# pcb.net
KiCad netlist of a schematic drawn in EAGLE
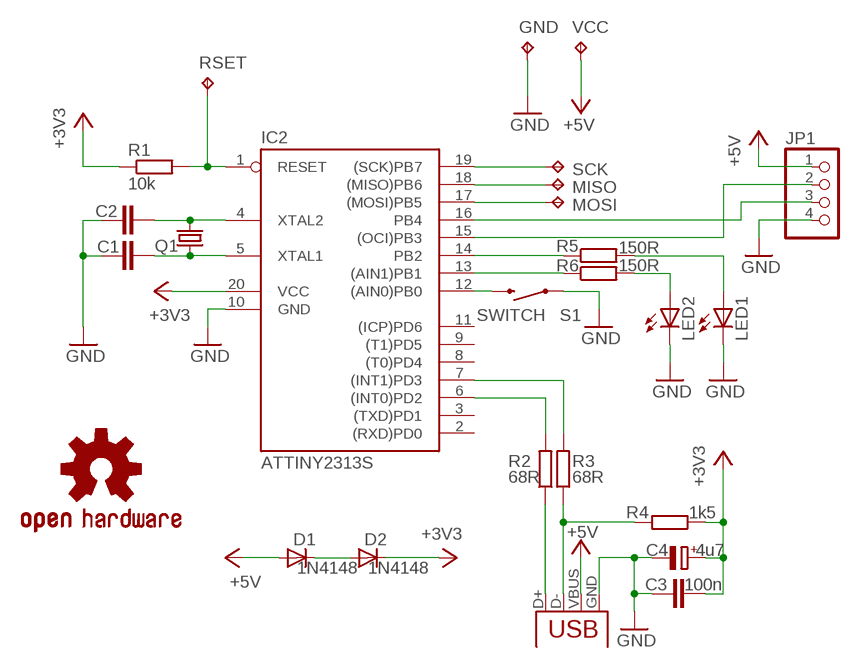
[diagram p0: schematic, sheet 1]

(export (version "E")
  (design (tool "Eeschema 10.0.6"))
  (components
    (comp (ref "C1")
      (value "C-EUC1206")
      (footprint "eagle-import:C1206")
      (libsource (lib "eagle-import") (part "C-EUC1206"))
    )
    (comp (ref "C2")
      (value "C-EUC1206")
      (footprint "eagle-import:C1206")
      (libsource (lib "eagle-import") (part "C-EUC1206"))
    )
    (comp (ref "C3")
      (value "100n")
      (footprint "eagle-import:C1206")
      (libsource (lib "eagle-import") (part "C-EUC1206"))
    )
    (comp (ref "C4")
      (value "4u7")
      (footprint "eagle-import:PANASONIC_B")
      (libsource (lib "eagle-import") (part "CPOL-EUB"))
    )
    (comp (ref "D1")
      (value "1N4148")
      (footprint "eagle-import:SMA-DIODE")
      (libsource (lib "eagle-import") (part "DIODESMA"))
    )
    (comp (ref "D2")
      (value "1N4148")
      (footprint "eagle-import:SMA-DIODE")
      (libsource (lib "eagle-import") (part "DIODESMA"))
    )
    (comp (ref "GND")
      (value "TPB2,54")
      (footprint "eagle-import:B2,54")
      (libsource (lib "eagle-import") (part "TPB2,54"))
    )
    (comp (ref "IC2")
      (value "ATTINY2313S")
      (footprint "eagle-import:SO20L")
      (libsource (lib "eagle-import") (part "AT90S2313S"))
    )
    (comp (ref "JP1")
      (value "PINHD-1X4_2.54")
      (footprint "eagle-import:1X04")
      (libsource (lib "eagle-import") (part "PINHD-1X4_2.54"))
    )
    (comp (ref "LED1")
      (value "LED1206")
      (footprint "eagle-import:LED-1206")
      (libsource (lib "eagle-import") (part "LED1206"))
    )
    (comp (ref "LED2")
      (value "LED1206")
      (footprint "eagle-import:LED-1206")
      (libsource (lib "eagle-import") (part "LED1206"))
    )
    (comp (ref "LOGO1")
      (value "OSHW-LOGOM")
      (footprint "eagle-import:OSHW-LOGO-M")
      (libsource (lib "eagle-import") (part "OSHW-LOGOM"))
    )
    (comp (ref "MISO")
      (value "TPB2,54")
      (footprint "eagle-import:B2,54")
      (libsource (lib "eagle-import") (part "TPB2,54"))
    )
    (comp (ref "MOSI")
      (value "TPB2,54")
      (footprint "eagle-import:B2,54")
      (libsource (lib "eagle-import") (part "TPB2,54"))
    )
    (comp (ref "Q1")
      (value "CRYSTALSMD")
      (footprint "eagle-import:HC49UP")
      (libsource (lib "eagle-import") (part "CRYSTALSMD"))
    )
    (comp (ref "R1")
      (value "10k")
      (footprint "eagle-import:R1206")
      (libsource (lib "eagle-import") (part "R-EU_R1206"))
    )
    (comp (ref "R2")
      (value "68R")
      (footprint "eagle-import:R1206")
      (libsource (lib "eagle-import") (part "R-EU_R1206"))
    )
    (comp (ref "R3")
      (value "68R")
      (footprint "eagle-import:R1206")
      (libsource (lib "eagle-import") (part "R-EU_R1206"))
    )
    (comp (ref "R4")
      (value "1k5")
      (footprint "eagle-import:R1206")
      (libsource (lib "eagle-import") (part "R-EU_R1206"))
    )
    (comp (ref "R5")
      (value "150R")
      (footprint "eagle-import:R1206")
      (libsource (lib "eagle-import") (part "R-EU_R1206"))
    )
    (comp (ref "R6")
      (value "150R")
      (footprint "eagle-import:R1206")
      (libsource (lib "eagle-import") (part "R-EU_R1206"))
    )
    (comp (ref "RSET")
      (value "TPB2,54")
      (footprint "eagle-import:B2,54")
      (libsource (lib "eagle-import") (part "TPB2,54"))
    )
    (comp (ref "S1")
      (value "SWITCH")
      (footprint "eagle-import:TACTILE-SWITCH-1101NE")
      (libsource (lib "eagle-import") (part "SWITCH-MOMENTARY-2-SMD-1101NE"))
    )
    (comp (ref "SCK")
      (value "TPB2,54")
      (footprint "eagle-import:B2,54")
      (libsource (lib "eagle-import") (part "TPB2,54"))
    )
    (comp (ref "VCC")
      (value "TPB2,54")
      (footprint "eagle-import:B2,54")
      (libsource (lib "eagle-import") (part "TPB2,54"))
    )
    (comp (ref "X1")
      (value "USB-MICROB")
      (footprint "eagle-import:USB-MICROB")
      (libsource (lib "eagle-import") (part "USB-MICROB"))
    )
  )
  (nets
    (net (code "1") (name "+3V3") (class "Default")
      (node (ref "C3") (pin "2") (pinfunction "2_2") (pintype "passive"))
      (node (ref "C4") (pin "+") (pinfunction "+_+") (pintype "passive"))
      (node (ref "D2") (pin "C") (pinfunction "C_C") (pintype "passive"))
      (node (ref "IC2") (pin "20") (pinfunction "VCC_20") (pintype "power_in"))
      (node (ref "R1") (pin "1") (pinfunction "1_1") (pintype "passive"))
      (node (ref "R4") (pin "1") (pinfunction "1_1") (pintype "passive"))
    )
    (net (code "2") (name "+5V") (class "Default")
      (node (ref "D1") (pin "A") (pinfunction "A_A") (pintype "passive"))
      (node (ref "JP1") (pin "1") (pinfunction "1_1") (pintype "passive"))
      (node (ref "VCC") (pin "TP") (pinfunction "TP_TP") (pintype "input"))
      (node (ref "X1") (pin "VBUS") (pinfunction "VBUS_VBUS") (pintype "bidirectional"))
    )
    (net (code "3") (name "GND") (class "Default")
      (node (ref "C1") (pin "1") (pinfunction "1_1") (pintype "passive"))
      (node (ref "C2") (pin "1") (pinfunction "1_1") (pintype "passive"))
      (node (ref "C3") (pin "1") (pinfunction "1_1") (pintype "passive"))
      (node (ref "C4") (pin "-") (pinfunction "-_-") (pintype "passive"))
      (node (ref "GND") (pin "TP") (pinfunction "TP_TP") (pintype "input"))
      (node (ref "IC2") (pin "10") (pinfunction "GND_10") (pintype "power_in"))
      (node (ref "JP1") (pin "4") (pinfunction "4_4") (pintype "passive"))
      (node (ref "LED1") (pin "C") (pinfunction "C_C") (pintype "passive"))
      (node (ref "LED2") (pin "C") (pinfunction "C_C") (pintype "passive"))
      (node (ref "S1") (pin "P$1") (pinfunction "1_P$1") (pintype "passive"))
      (node (ref "X1") (pin "GND") (pinfunction "GND_GND") (pintype "bidirectional"))
    )
    (net (code "4") (name "Net-(D1-PadC)") (class "Default")
      (node (ref "D1") (pin "C") (pinfunction "C_C") (pintype "passive"))
      (node (ref "D2") (pin "A") (pinfunction "A_A") (pintype "passive"))
    )
    (net (code "5") (name "Net-(IC2-(AIN0)PB0)") (class "Default")
      (node (ref "IC2") (pin "12") (pinfunction "(AIN0)PB0_12") (pintype "bidirectional"))
      (node (ref "S1") (pin "P$2") (pinfunction "2_P$2") (pintype "passive"))
    )
    (net (code "6") (name "Net-(IC2-(AIN1)PB1)") (class "Default")
      (node (ref "IC2") (pin "13") (pinfunction "(AIN1)PB1_13") (pintype "bidirectional"))
      (node (ref "R6") (pin "1") (pinfunction "1_1") (pintype "passive"))
    )
    (net (code "7") (name "Net-(IC2-(INT0)PD2)") (class "Default")
      (node (ref "IC2") (pin "6") (pinfunction "(INT0)PD2_6") (pintype "bidirectional"))
      (node (ref "R2") (pin "2") (pinfunction "2_2") (pintype "passive"))
    )
    (net (code "8") (name "Net-(IC2-(INT1)PD3)") (class "Default")
      (node (ref "IC2") (pin "7") (pinfunction "(INT1)PD3_7") (pintype "bidirectional"))
      (node (ref "R3") (pin "2") (pinfunction "2_2") (pintype "passive"))
    )
    (net (code "9") (name "Net-(IC2-(MISO)PB6)") (class "Default")
      (node (ref "IC2") (pin "18") (pinfunction "(MISO)PB6_18") (pintype "bidirectional"))
      (node (ref "MISO") (pin "TP") (pinfunction "TP_TP") (pintype "input"))
    )
    (net (code "10") (name "Net-(IC2-(MOSI)PB5)") (class "Default")
      (node (ref "IC2") (pin "17") (pinfunction "(MOSI)PB5_17") (pintype "bidirectional"))
      (node (ref "MOSI") (pin "TP") (pinfunction "TP_TP") (pintype "input"))
    )
    (net (code "11") (name "Net-(IC2-(OCI)PB3)") (class "Default")
      (node (ref "IC2") (pin "15") (pinfunction "(OCI)PB3_15") (pintype "bidirectional"))
      (node (ref "JP1") (pin "2") (pinfunction "2_2") (pintype "passive"))
    )
    (net (code "12") (name "Net-(IC2-(SCK)PB7)") (class "Default")
      (node (ref "IC2") (pin "19") (pinfunction "(SCK)PB7_19") (pintype "bidirectional"))
      (node (ref "SCK") (pin "TP") (pinfunction "TP_TP") (pintype "input"))
    )
    (net (code "13") (name "Net-(IC2-PB2)") (class "Default")
      (node (ref "IC2") (pin "14") (pinfunction "PB2_14") (pintype "bidirectional"))
      (node (ref "R5") (pin "1") (pinfunction "1_1") (pintype "passive"))
    )
    (net (code "14") (name "Net-(IC2-PB4)") (class "Default")
      (node (ref "IC2") (pin "16") (pinfunction "PB4_16") (pintype "bidirectional"))
      (node (ref "JP1") (pin "3") (pinfunction "3_3") (pintype "passive"))
    )
    (net (code "15") (name "Net-(IC2-RESET)") (class "Default")
      (node (ref "IC2") (pin "1") (pinfunction "RESET_1") (pintype "bidirectional"))
      (node (ref "R1") (pin "2") (pinfunction "2_2") (pintype "passive"))
      (node (ref "RSET") (pin "TP") (pinfunction "TP_TP") (pintype "input"))
    )
    (net (code "16") (name "Net-(IC2-XTAL1)") (class "Default")
      (node (ref "C1") (pin "2") (pinfunction "2_2") (pintype "passive"))
      (node (ref "IC2") (pin "5") (pinfunction "XTAL1_5") (pintype "bidirectional"))
      (node (ref "Q1") (pin "1") (pinfunction "1_1") (pintype "passive"))
    )
    (net (code "17") (name "Net-(IC2-XTAL2)") (class "Default")
      (node (ref "C2") (pin "2") (pinfunction "2_2") (pintype "passive"))
      (node (ref "IC2") (pin "4") (pinfunction "XTAL2_4") (pintype "bidirectional"))
      (node (ref "Q1") (pin "2") (pinfunction "2_2") (pintype "passive"))
    )
    (net (code "18") (name "Net-(LED1-PadA)") (class "Default")
      (node (ref "LED1") (pin "A") (pinfunction "A_A") (pintype "passive"))
      (node (ref "R5") (pin "2") (pinfunction "2_2") (pintype "passive"))
    )
    (net (code "19") (name "Net-(LED2-PadA)") (class "Default")
      (node (ref "LED2") (pin "A") (pinfunction "A_A") (pintype "passive"))
      (node (ref "R6") (pin "2") (pinfunction "2_2") (pintype "passive"))
    )
    (net (code "20") (name "Net-(R2-Pad1)") (class "Default")
      (node (ref "R2") (pin "1") (pinfunction "1_1") (pintype "passive"))
      (node (ref "X1") (pin "D+") (pinfunction "D+_D+") (pintype "bidirectional"))
    )
    (net (code "21") (name "Net-(R3-Pad1)") (class "Default")
      (node (ref "R3") (pin "1") (pinfunction "1_1") (pintype "passive"))
      (node (ref "R4") (pin "2") (pinfunction "2_2") (pintype "passive"))
      (node (ref "X1") (pin "D-") (pinfunction "D-_D-") (pintype "bidirectional"))
    )
    (net (code "22") (name "unconnected-(IC2-(ICP)PD6-Pad11)") (class "Default")
      (node (ref "IC2") (pin "11") (pinfunction "(ICP)PD6_11") (pintype "bidirectional"))
    )
    (net (code "23") (name "unconnected-(IC2-(RXD)PD0-Pad2)") (class "Default")
      (node (ref "IC2") (pin "2") (pinfunction "(RXD)PD0_2") (pintype "bidirectional"))
    )
    (net (code "24") (name "unconnected-(IC2-(T0)PD4-Pad8)") (class "Default")
      (node (ref "IC2") (pin "8") (pinfunction "(T0)PD4_8") (pintype "bidirectional"))
    )
    (net (code "25") (name "unconnected-(IC2-(T1)PD5-Pad9)") (class "Default")
      (node (ref "IC2") (pin "9") (pinfunction "(T1)PD5_9") (pintype "bidirectional"))
    )
    (net (code "26") (name "unconnected-(IC2-(TXD)PD1-Pad3)") (class "Default")
      (node (ref "IC2") (pin "3") (pinfunction "(TXD)PD1_3") (pintype "bidirectional"))
    )
  )
)
